# BLDC_Motor_Reversal_Rev2.net
KiCad netlist of a schematic drawn in Altium Designer
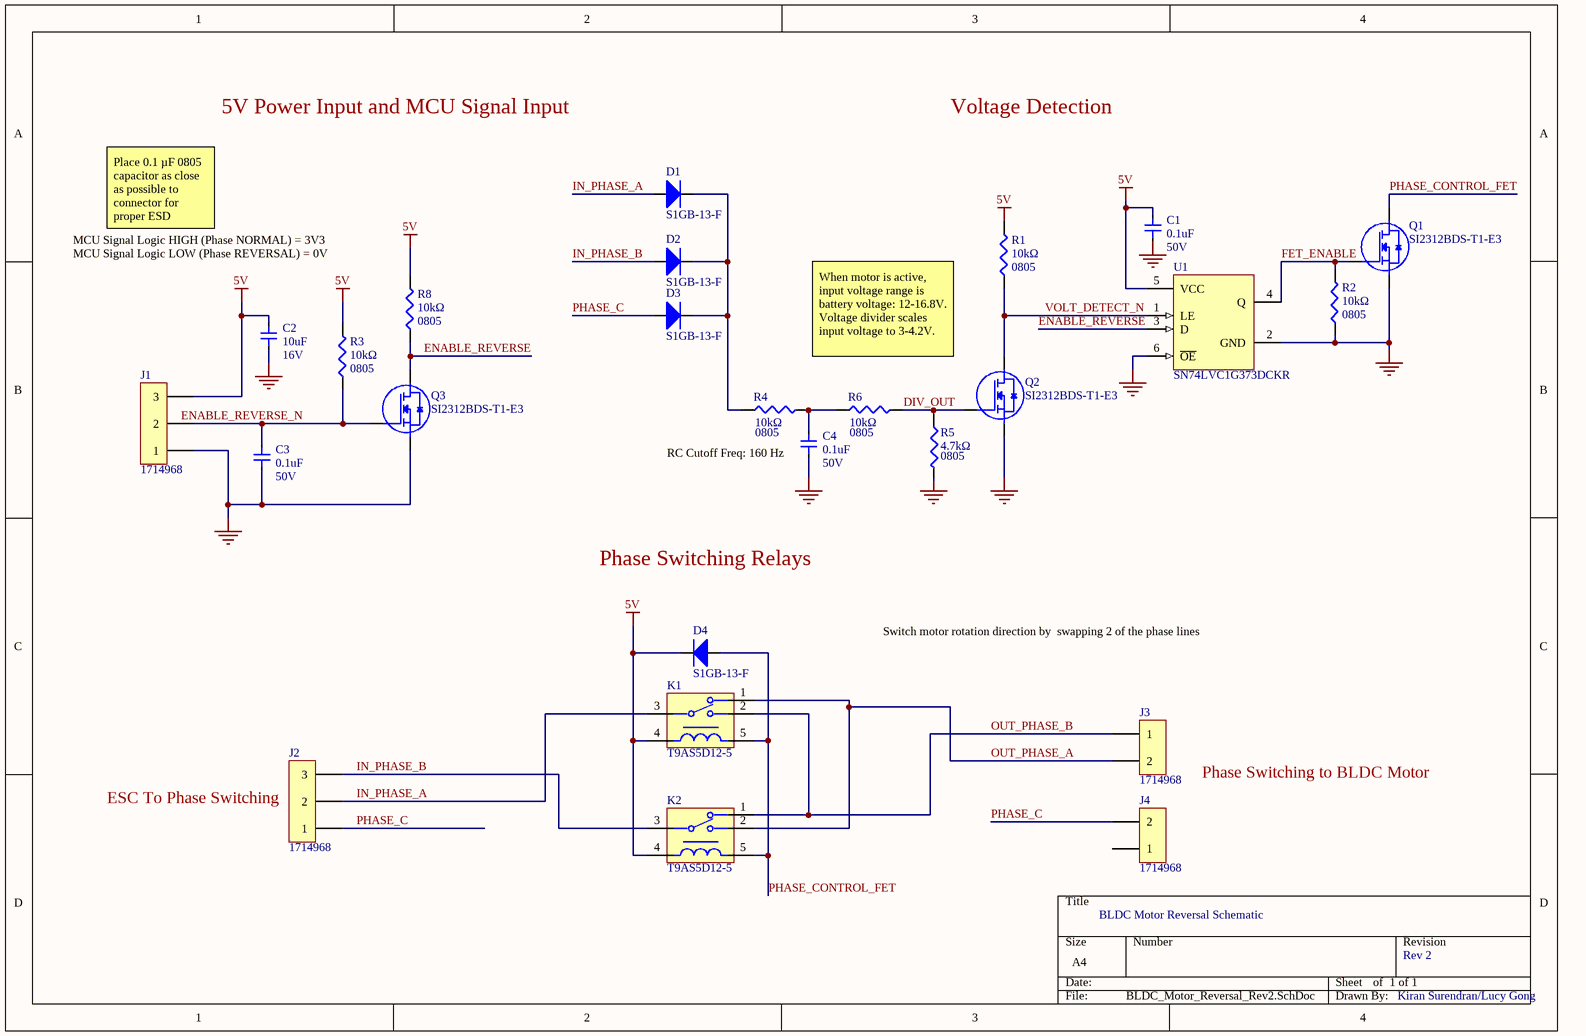
[diagram p0: BLDC_Motor_Reversal_Rev2.SchDoc]

(export (version "E")
  (design (tool "Eeschema 10.0.6"))
  (components
    (comp (ref "C1")
      (value "C0805C104K5RACTU")
      (footprint "C0805C104K5RACTU")
      (description "CAP CER 0.1UF 50V X7R 0805")
      (fields (field (name "VOLTAGE RATING") "50V") (field (name "CAPACITANCE") "0.1uF"))
      (libsource (lib "BLDC_Motor_SchLib") (part "C0805C104K5RACTU"))
    )
    (comp (ref "C2")
      (value "C0805C106K4PACTU")
      (footprint "C0805C106K4PACTU")
      (description "CERAMIC CAPACITOR, 10UF, 16V, X5R, 10%, 0805")
      (fields (field (name "VOLTAGE RATING") "16V") (field (name "CAPACITANCE") "10uF"))
      (libsource (lib "BLDC_Motor_Lib") (part "C0805C106K4PACTU"))
    )
    (comp (ref "C3")
      (value "C0805C104K5RACTU")
      (footprint "C0805C104K5RACTU")
      (description "CAP CER 0.1UF 50V X7R 0805")
      (fields (field (name "VOLTAGE RATING") "50V") (field (name "CAPACITANCE") "0.1uF"))
      (libsource (lib "BLDC_Motor_SchLib") (part "C0805C104K5RACTU"))
    )
    (comp (ref "C4")
      (value "C0805C104K5RACTU")
      (footprint "C0805C104K5RACTU")
      (description "CAP CER 0.1UF 50V X7R 0805")
      (fields (field (name "VOLTAGE RATING") "50V") (field (name "CAPACITANCE") "0.1uF"))
      (libsource (lib "BLDC_Motor_SchLib") (part "C0805C104K5RACTU"))
    )
    (comp (ref "D1")
      (value "S1GB-13-F")
      (footprint "S1GB-13-F")
      (description "Flyback Diode for SPDT")
      (libsource (lib "BLDC_Motor_Lib") (part "S1GB-13-F"))
    )
    (comp (ref "D2")
      (value "S1GB-13-F")
      (footprint "S1GB-13-F")
      (description "Flyback Diode for SPDT")
      (libsource (lib "BLDC_Motor_Lib") (part "S1GB-13-F"))
    )
    (comp (ref "D3")
      (value "S1GB-13-F")
      (footprint "S1GB-13-F")
      (description "Flyback Diode for SPDT")
      (libsource (lib "BLDC_Motor_Lib") (part "S1GB-13-F"))
    )
    (comp (ref "D4")
      (value "S1GB-13-F")
      (footprint "S1GB-13-F")
      (description "DIODE GEN PURP 400V 1A SMB")
      (libsource (lib "BLDC_Motor_SchLib") (part "S1GB-13-F"))
    )
    (comp (ref "J1")
      (value "1714968")
      (footprint "796740-3")
      (description "TERM BLK 3P SIDE ENT 6.35MM PCB")
      (libsource (lib "BLDC_Motor_SchLib") (part "1714968"))
    )
    (comp (ref "J2")
      (value "1714968")
      (footprint "796740-3")
      (description "TERM BLK 3P SIDE ENT 6.35MM PCB")
      (libsource (lib "BLDC_Motor_SchLib") (part "1714968"))
    )
    (comp (ref "J3")
      (value "1714968")
      (footprint "1714955")
      (description "TERM BLK 2P SIDE ENT 6.35MM PCB")
      (fields (field (name "MANUFACTURER") "Phoenix Contact"))
      (libsource (lib "BLDC_Motor_SchLib") (part "1714955"))
    )
    (comp (ref "J4")
      (value "1714968")
      (footprint "1714955")
      (description "TERM BLK 2P SIDE ENT 6.35MM PCB")
      (fields (field (name "MANUFACTURER") "Phoenix Contact"))
      (libsource (lib "") (part "1714955_1"))
    )
    (comp (ref "K1")
      (value "T9AS5D12-5")
      (footprint "T9AS5D12-5")
      (description "RELAY GEN PURPOSE SPDT 20A 5V")
      (libsource (lib "BLDC_Motor_Lib") (part "T9AS5D12-5"))
    )
    (comp (ref "K2")
      (value "T9AS5D12-5")
      (footprint "T9AS5D12-5")
      (description "RELAY GEN PURPOSE SPDT 20A 5V")
      (libsource (lib "BLDC_Motor_Lib") (part "T9AS5D12-5"))
    )
    (comp (ref "Q1")
      (value "SI2312BDS-T1-E3")
      (footprint "SI2312BDS-T1-E3")
      (description "MOSFET")
      (libsource (lib "BLDC_Motor_Lib") (part "SI2312BDS-T1-E3"))
    )
    (comp (ref "Q2")
      (value "SI2312BDS-T1-E3")
      (footprint "SI2312BDS-T1-E3")
      (description "MOSFET N-CH 20V 3.9A SOT23-3")
      (libsource (lib "BLDC_Motor_SchLib") (part "SI2312BDS-T1-E3"))
    )
    (comp (ref "Q3")
      (value "SI2312BDS-T1-E3")
      (footprint "SI2312BDS-T1-E3")
      (description "MOSFET N-CH 20V 3.9A SOT23-3")
      (libsource (lib "BLDC_Motor_SchLib") (part "SI2312BDS-T1-E3"))
    )
    (comp (ref "R1")
      (value "RC0805JR-0710KL")
      (footprint "RC0805JR-0710KL")
      (description "RES SMD 10K OHM 5% 1/8W 0805")
      (fields
        (field (name "TOLERANCE") "5%")
        (field (name "PACKAGE") "0805")
        (field (name "RESISTANCE") "10kΩ")
      )
      (libsource (lib "BLDC_Motor_SchLib") (part "RC0805JR-0710KL"))
    )
    (comp (ref "R2")
      (value "RC0805JR-0710KL")
      (footprint "RC0805JR-0710KL")
      (description "RES SMD 10K OHM 5% 1/8W 0805")
      (fields
        (field (name "TOLERANCE") "5%")
        (field (name "PACKAGE") "0805")
        (field (name "RESISTANCE") "10kΩ")
      )
      (libsource (lib "BLDC_Motor_SchLib") (part "RC0805JR-0710KL"))
    )
    (comp (ref "R3")
      (value "RC0805JR-0710KL")
      (footprint "RC0805JR-0710KL")
      (description "RES SMD 10K OHM 5% 1/8W 0805")
      (fields
        (field (name "TOLERANCE") "5%")
        (field (name "PACKAGE") "0805")
        (field (name "RESISTANCE") "10kΩ")
      )
      (libsource (lib "BLDC_Motor_SchLib") (part "RC0805JR-0710KL"))
    )
    (comp (ref "R4")
      (value "RC0805JR-0710KL")
      (footprint "RC0805JR-0710KL")
      (description "RES SMD 10K OHM 5% 1/8W 0805")
      (fields
        (field (name "TOLERANCE") "5%")
        (field (name "PACKAGE") "0805")
        (field (name "RESISTANCE") "10kΩ")
      )
      (libsource (lib "BLDC_Motor_SchLib") (part "RC0805JR-0710KL"))
    )
    (comp (ref "R5")
      (value "RC0805JR-0747KL")
      (footprint "RC0805JR-0747KL")
      (description "RES SMD 4.7K OHM 5% 1/8W 0805")
      (fields (field (name "PACKAGE") "0805") (field (name "RESISTANCE") "4.7kΩ"))
      (libsource (lib "BLDC_Motor_SchLib") (part "RC0805JR-074K7L"))
    )
    (comp (ref "R6")
      (value "RC0805JR-0710KL")
      (footprint "RC0805JR-0710KL")
      (description "RES SMD 10K OHM 5% 1/8W 0805")
      (fields
        (field (name "TOLERANCE") "5%")
        (field (name "PACKAGE") "0805")
        (field (name "RESISTANCE") "10kΩ")
      )
      (libsource (lib "BLDC_Motor_SchLib") (part "RC0805JR-0710KL"))
    )
    (comp (ref "R8")
      (value "RC0805JR-0710KL")
      (footprint "RC0805JR-0710KL")
      (description "RES SMD 10K OHM 5% 1/8W 0805")
      (fields
        (field (name "TOLERANCE") "5%")
        (field (name "PACKAGE") "0805")
        (field (name "RESISTANCE") "10kΩ")
      )
      (libsource (lib "BLDC_Motor_SchLib") (part "RC0805JR-0710KL"))
    )
    (comp (ref "U1")
      (value "SN74LVC1G373DCKR")
      (footprint "DCK0006A_N")
      (description "IC LTCH D-TYP SGL 3-OUT SC70-6")
      (fields (field (name "MANUFACTURER") "Texas Instruments"))
      (libsource (lib "BLDC_Motor_SchLib") (part "SN74LVC1G373DCKR"))
    )
  )
  (nets
    (net (code "1") (name "/DIV_OUT") (class "Default")
      (node (ref "Q2") (pin "1") (pinfunction "Gate_1") (pintype "passive"))
      (node (ref "R5") (pin "1") (pintype "passive"))
      (node (ref "R6") (pin "2") (pintype "passive"))
    )
    (net (code "2") (name "/ENABLE_REVERSE") (class "Default")
      (node (ref "Q3") (pin "3") (pinfunction "Drain_3") (pintype "passive"))
      (node (ref "R8") (pin "1") (pintype "passive"))
      (node (ref "U1") (pin "3") (pinfunction "D_3") (pintype "input"))
    )
    (net (code "4") (name "/FET_ENABLE") (class "Default")
      (node (ref "Q1") (pin "1") (pinfunction "Gate_1") (pintype "passive"))
      (node (ref "R2") (pin "2") (pintype "passive"))
      (node (ref "U1") (pin "4") (pinfunction "Q_4") (pintype "tri_state"))
    )
    (net (code "5") (name "/IN_PHASE_A") (class "Default")
      (node (ref "D1") (pin "1") (pinfunction "+_1") (pintype "passive"))
      (node (ref "J2") (pin "2") (pinfunction "2_2") (pintype "passive"))
      (node (ref "K1") (pin "3") (pinfunction "COM_3") (pintype "passive"))
    )
    (net (code "6") (name "/IN_PHASE_B") (class "Default")
      (node (ref "D2") (pin "1") (pinfunction "+_1") (pintype "passive"))
      (node (ref "J2") (pin "3") (pinfunction "3_3") (pintype "passive"))
      (node (ref "K2") (pin "3") (pinfunction "COM_3") (pintype "passive"))
    )
    (net (code "7") (name "/OUT_PHASE_A") (class "Default")
      (node (ref "J3") (pin "2") (pinfunction "2_2") (pintype "passive"))
      (node (ref "K1") (pin "1") (pinfunction "NC_1") (pintype "passive"))
      (node (ref "K2") (pin "2") (pinfunction "NO_2") (pintype "passive"))
    )
    (net (code "8") (name "/OUT_PHASE_B") (class "Default")
      (node (ref "J3") (pin "1") (pinfunction "1_1") (pintype "passive"))
      (node (ref "K1") (pin "2") (pinfunction "NO_2") (pintype "passive"))
      (node (ref "K2") (pin "1") (pinfunction "NC_1") (pintype "passive"))
    )
    (net (code "9") (name "/PHASE_C") (class "Default")
      (node (ref "D3") (pin "1") (pinfunction "+_1") (pintype "passive"))
      (node (ref "J2") (pin "1") (pinfunction "1_1") (pintype "passive"))
      (node (ref "J4") (pin "2") (pinfunction "2_2") (pintype "passive"))
    )
    (net (code "10") (name "/PHASE_CONTROL_FET") (class "Default")
      (node (ref "D4") (pin "2") (pinfunction "+_2") (pintype "passive"))
      (node (ref "K1") (pin "5") (pinfunction "5_5") (pintype "passive"))
      (node (ref "K2") (pin "5") (pinfunction "5_5") (pintype "passive"))
      (node (ref "Q1") (pin "3") (pinfunction "Drain_3") (pintype "passive"))
    )
    (net (code "11") (name "/VOLT_DETECT_N") (class "Default")
      (node (ref "Q2") (pin "3") (pinfunction "Drain_3") (pintype "passive"))
      (node (ref "R1") (pin "1") (pintype "passive"))
      (node (ref "U1") (pin "1") (pinfunction "LE_1") (pintype "input"))
    )
    (net (code "12") (name "5V") (class "Default")
      (node (ref "C1") (pin "2") (pintype "passive"))
      (node (ref "C2") (pin "2") (pintype "passive"))
      (node (ref "D4") (pin "1") (pinfunction "-_1") (pintype "passive"))
      (node (ref "J1") (pin "3") (pinfunction "3_3") (pintype "passive"))
      (node (ref "K1") (pin "4") (pinfunction "4_4") (pintype "passive"))
      (node (ref "K2") (pin "4") (pinfunction "4_4") (pintype "passive"))
      (node (ref "R1") (pin "2") (pintype "passive"))
      (node (ref "R3") (pin "2") (pintype "passive"))
      (node (ref "R8") (pin "2") (pintype "passive"))
      (node (ref "U1") (pin "5") (pinfunction "VCC_5") (pintype "power_in"))
    )
    (net (code "13") (name "GND") (class "Default")
      (node (ref "C1") (pin "1") (pintype "passive"))
      (node (ref "C2") (pin "1") (pintype "passive"))
      (node (ref "C3") (pin "1") (pintype "passive"))
      (node (ref "C4") (pin "1") (pintype "passive"))
      (node (ref "J1") (pin "1") (pinfunction "1_1") (pintype "passive"))
      (node (ref "Q1") (pin "2") (pinfunction "Source_2") (pintype "passive"))
      (node (ref "Q2") (pin "2") (pinfunction "Source_2") (pintype "passive"))
      (node (ref "Q3") (pin "2") (pinfunction "Source_2") (pintype "passive"))
      (node (ref "R2") (pin "1") (pintype "passive"))
      (node (ref "R5") (pin "2") (pintype "passive"))
      (node (ref "U1") (pin "2") (pinfunction "GND_2") (pintype "power_in"))
      (node (ref "U1") (pin "6") (pinfunction "~{OE}_6") (pintype "input"))
    )
    (net (code "14") (name "Net-(C4-Pad2)") (class "Default")
      (node (ref "C4") (pin "2") (pintype "passive"))
      (node (ref "R4") (pin "2") (pintype "passive"))
      (node (ref "R6") (pin "1") (pintype "passive"))
    )
    (net (code "15") (name "Net-(D1--)") (class "Default")
      (node (ref "D1") (pin "2") (pinfunction "-_2") (pintype "passive"))
      (node (ref "D2") (pin "2") (pinfunction "-_2") (pintype "passive"))
      (node (ref "D3") (pin "2") (pinfunction "-_2") (pintype "passive"))
      (node (ref "R4") (pin "1") (pintype "passive"))
    )
    (net (code "16") (name "Net-(Q3-Gate)") (class "Default")
      (node (ref "C3") (pin "2") (pintype "passive"))
      (node (ref "J1") (pin "2") (pinfunction "2_2") (pintype "passive"))
      (node (ref "Q3") (pin "1") (pinfunction "Gate_1") (pintype "passive"))
      (node (ref "R3") (pin "1") (pintype "passive"))
    )
    (net (code "17") (name "unconnected-(J4-Pad1)") (class "Default")
      (node (ref "J4") (pin "1") (pinfunction "1_1") (pintype "passive"))
    )
  )
)
